# E-19_RGB_8x8_Display.net
KiCad netlist of a schematic drawn in Altium Designer
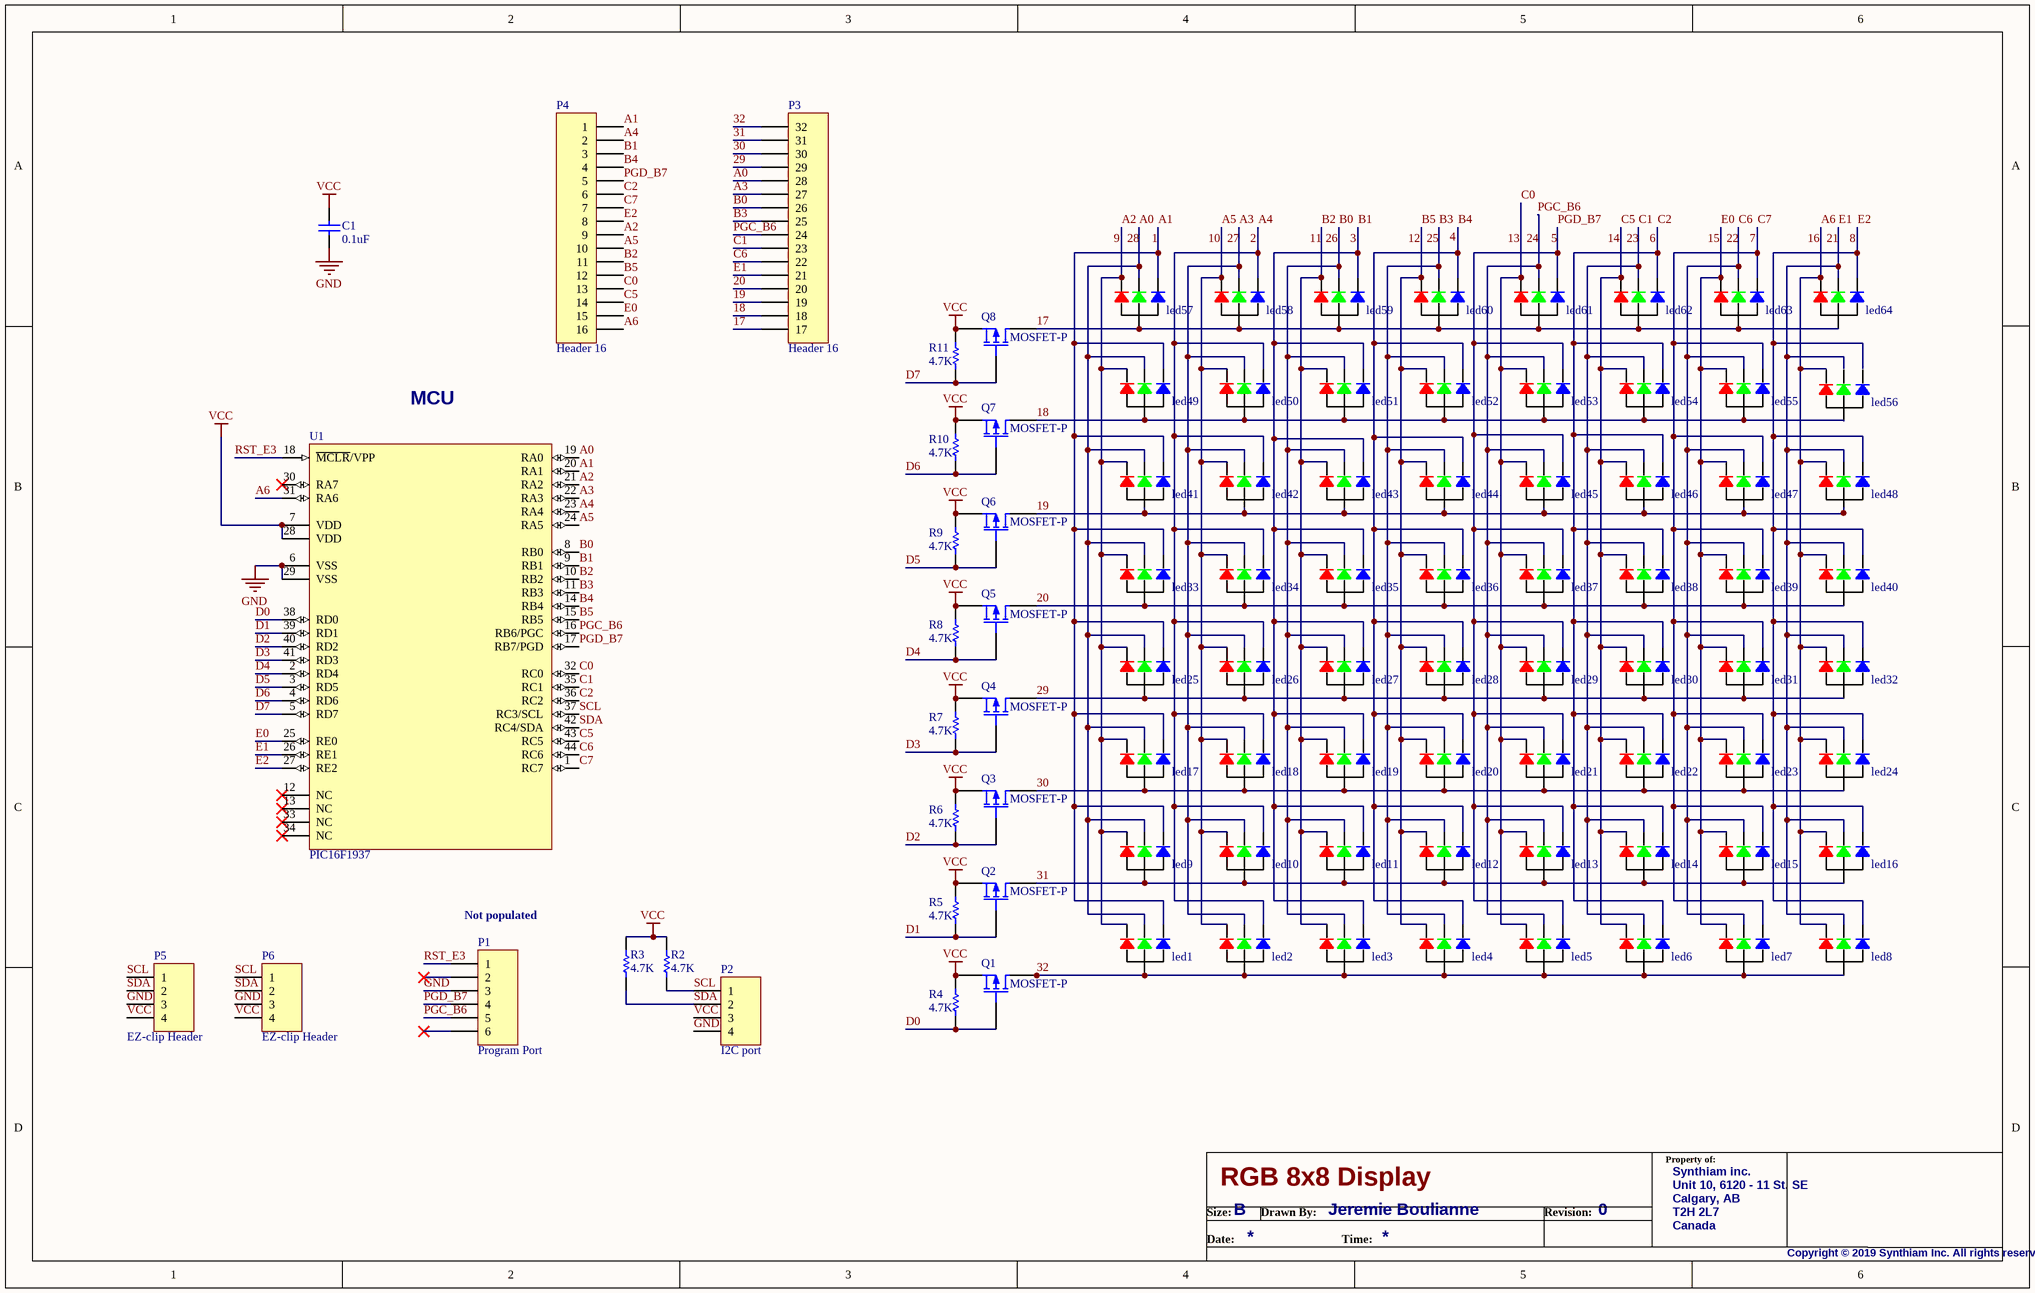
[diagram p0: E-19 RGB 8x8 Display.SchDoc]

(export (version "E")
  (design (tool "Eeschema 10.0.6"))
  (components
    (comp (ref "C1")
      (value "0.1uF")
      (footprint "0805 TIGHT")
      (description "Capacitor")
      (fields (field (name "Comment") "Cap") (field (name "PUBLISHER") "Altium Limited"))
      (libsource (lib "SB_Discrete") (part "Cap"))
    )
    (comp (ref "led1") (value "RGBLED-CA mini2") (libsource (lib "") (part "RGBLED-CA mini2_1")))
    (comp (ref "led2") (value "RGBLED-CA mini2") (libsource (lib "SB_Discrete") (part "RGBLED-CA mini2")))
    (comp (ref "led3") (value "RGBLED-CA mini2") (libsource (lib "SB_Discrete") (part "RGBLED-CA mini2")))
    (comp (ref "led4") (value "RGBLED-CA mini2") (libsource (lib "SB_Discrete") (part "RGBLED-CA mini2")))
    (comp (ref "led5") (value "RGBLED-CA mini2") (libsource (lib "SB_Discrete") (part "RGBLED-CA mini2")))
    (comp (ref "led6") (value "RGBLED-CA mini2") (libsource (lib "SB_Discrete") (part "RGBLED-CA mini2")))
    (comp (ref "led7") (value "RGBLED-CA mini2") (libsource (lib "SB_Discrete") (part "RGBLED-CA mini2")))
    (comp (ref "led8") (value "RGBLED-CA mini2") (libsource (lib "SB_Discrete") (part "RGBLED-CA mini2")))
    (comp (ref "led9") (value "RGBLED-CA mini2") (libsource (lib "SB_Discrete") (part "RGBLED-CA mini2")))
    (comp (ref "led10") (value "RGBLED-CA mini2") (libsource (lib "SB_Discrete") (part "RGBLED-CA mini2")))
    (comp (ref "led11") (value "RGBLED-CA mini2") (libsource (lib "SB_Discrete") (part "RGBLED-CA mini2")))
    (comp (ref "led12") (value "RGBLED-CA mini2") (libsource (lib "SB_Discrete") (part "RGBLED-CA mini2")))
    (comp (ref "led13") (value "RGBLED-CA mini2") (libsource (lib "SB_Discrete") (part "RGBLED-CA mini2")))
    (comp (ref "led14") (value "RGBLED-CA mini2") (libsource (lib "SB_Discrete") (part "RGBLED-CA mini2")))
    (comp (ref "led15") (value "RGBLED-CA mini2") (libsource (lib "SB_Discrete") (part "RGBLED-CA mini2")))
    (comp (ref "led16") (value "RGBLED-CA mini2") (libsource (lib "SB_Discrete") (part "RGBLED-CA mini2")))
    (comp (ref "led17") (value "RGBLED-CA mini2") (libsource (lib "SB_Discrete") (part "RGBLED-CA mini2")))
    (comp (ref "led18") (value "RGBLED-CA mini2") (libsource (lib "SB_Discrete") (part "RGBLED-CA mini2")))
    (comp (ref "led19") (value "RGBLED-CA mini2") (libsource (lib "SB_Discrete") (part "RGBLED-CA mini2")))
    (comp (ref "led20") (value "RGBLED-CA mini2") (libsource (lib "SB_Discrete") (part "RGBLED-CA mini2")))
    (comp (ref "led21") (value "RGBLED-CA mini2") (libsource (lib "SB_Discrete") (part "RGBLED-CA mini2")))
    (comp (ref "led22") (value "RGBLED-CA mini2") (libsource (lib "SB_Discrete") (part "RGBLED-CA mini2")))
    (comp (ref "led23") (value "RGBLED-CA mini2") (libsource (lib "SB_Discrete") (part "RGBLED-CA mini2")))
    (comp (ref "led24") (value "RGBLED-CA mini2") (libsource (lib "SB_Discrete") (part "RGBLED-CA mini2")))
    (comp (ref "led25") (value "RGBLED-CA mini2") (libsource (lib "SB_Discrete") (part "RGBLED-CA mini2")))
    (comp (ref "led26") (value "RGBLED-CA mini2") (libsource (lib "SB_Discrete") (part "RGBLED-CA mini2")))
    (comp (ref "led27") (value "RGBLED-CA mini2") (libsource (lib "SB_Discrete") (part "RGBLED-CA mini2")))
    (comp (ref "led28") (value "RGBLED-CA mini2") (libsource (lib "SB_Discrete") (part "RGBLED-CA mini2")))
    (comp (ref "led29") (value "RGBLED-CA mini2") (libsource (lib "SB_Discrete") (part "RGBLED-CA mini2")))
    (comp (ref "led30") (value "RGBLED-CA mini2") (libsource (lib "SB_Discrete") (part "RGBLED-CA mini2")))
    (comp (ref "led31") (value "RGBLED-CA mini2") (libsource (lib "SB_Discrete") (part "RGBLED-CA mini2")))
    (comp (ref "led32") (value "RGBLED-CA mini2") (libsource (lib "SB_Discrete") (part "RGBLED-CA mini2")))
    (comp (ref "led33") (value "RGBLED-CA mini2") (libsource (lib "SB_Discrete") (part "RGBLED-CA mini2")))
    (comp (ref "led34") (value "RGBLED-CA mini2") (libsource (lib "SB_Discrete") (part "RGBLED-CA mini2")))
    (comp (ref "led35") (value "RGBLED-CA mini2") (libsource (lib "SB_Discrete") (part "RGBLED-CA mini2")))
    (comp (ref "led36") (value "RGBLED-CA mini2") (libsource (lib "SB_Discrete") (part "RGBLED-CA mini2")))
    (comp (ref "led37") (value "RGBLED-CA mini2") (libsource (lib "SB_Discrete") (part "RGBLED-CA mini2")))
    (comp (ref "led38") (value "RGBLED-CA mini2") (libsource (lib "SB_Discrete") (part "RGBLED-CA mini2")))
    (comp (ref "led39") (value "RGBLED-CA mini2") (libsource (lib "SB_Discrete") (part "RGBLED-CA mini2")))
    (comp (ref "led40") (value "RGBLED-CA mini2") (libsource (lib "SB_Discrete") (part "RGBLED-CA mini2")))
    (comp (ref "led41") (value "RGBLED-CA mini2") (libsource (lib "SB_Discrete") (part "RGBLED-CA mini2")))
    (comp (ref "led42") (value "RGBLED-CA mini2") (libsource (lib "SB_Discrete") (part "RGBLED-CA mini2")))
    (comp (ref "led43") (value "RGBLED-CA mini2") (libsource (lib "SB_Discrete") (part "RGBLED-CA mini2")))
    (comp (ref "led44") (value "RGBLED-CA mini2") (libsource (lib "SB_Discrete") (part "RGBLED-CA mini2")))
    (comp (ref "led45") (value "RGBLED-CA mini2") (libsource (lib "SB_Discrete") (part "RGBLED-CA mini2")))
    (comp (ref "led46") (value "RGBLED-CA mini2") (libsource (lib "SB_Discrete") (part "RGBLED-CA mini2")))
    (comp (ref "led47") (value "RGBLED-CA mini2") (libsource (lib "SB_Discrete") (part "RGBLED-CA mini2")))
    (comp (ref "led48") (value "RGBLED-CA mini2") (libsource (lib "SB_Discrete") (part "RGBLED-CA mini2")))
    (comp (ref "led49") (value "RGBLED-CA mini2") (libsource (lib "SB_Discrete") (part "RGBLED-CA mini2")))
    (comp (ref "led50") (value "RGBLED-CA mini2") (libsource (lib "SB_Discrete") (part "RGBLED-CA mini2")))
    (comp (ref "led51") (value "RGBLED-CA mini2") (libsource (lib "SB_Discrete") (part "RGBLED-CA mini2")))
    (comp (ref "led52") (value "RGBLED-CA mini2") (libsource (lib "SB_Discrete") (part "RGBLED-CA mini2")))
    (comp (ref "led53") (value "RGBLED-CA mini2") (libsource (lib "SB_Discrete") (part "RGBLED-CA mini2")))
    (comp (ref "led54") (value "RGBLED-CA mini2") (libsource (lib "SB_Discrete") (part "RGBLED-CA mini2")))
    (comp (ref "led55") (value "RGBLED-CA mini2") (libsource (lib "SB_Discrete") (part "RGBLED-CA mini2")))
    (comp (ref "led56") (value "RGBLED-CA mini2") (libsource (lib "SB_Discrete") (part "RGBLED-CA mini2")))
    (comp (ref "led57") (value "RGBLED-CA mini2") (libsource (lib "SB_Discrete") (part "RGBLED-CA mini2")))
    (comp (ref "led58") (value "RGBLED-CA mini2") (libsource (lib "SB_Discrete") (part "RGBLED-CA mini2")))
    (comp (ref "led59") (value "RGBLED-CA mini2") (libsource (lib "SB_Discrete") (part "RGBLED-CA mini2")))
    (comp (ref "led60") (value "RGBLED-CA mini2") (libsource (lib "SB_Discrete") (part "RGBLED-CA mini2")))
    (comp (ref "led61") (value "RGBLED-CA mini2") (libsource (lib "SB_Discrete") (part "RGBLED-CA mini2")))
    (comp (ref "led62") (value "RGBLED-CA mini2") (libsource (lib "SB_Discrete") (part "RGBLED-CA mini2")))
    (comp (ref "led63") (value "RGBLED-CA mini2") (libsource (lib "SB_Discrete") (part "RGBLED-CA mini2")))
    (comp (ref "led64") (value "RGBLED-CA mini2") (libsource (lib "SB_Discrete") (part "RGBLED-CA mini2")))
    (comp (ref "P1")
      (value "Program Port")
      (footprint "HDR1X6")
      (description "Header, 6-Pin")
      (fields (field (name "PUBLISHER") "Altium Limited"))
      (libsource (lib "Miscellaneous Connectors") (part "Header 6"))
    )
    (comp (ref "P2")
      (value "I2C port")
      (footprint "JST-PH 4pin")
      (description "Header, 4-Pin")
      (fields (field (name "PUBLISHER") "Altium Limited"))
      (libsource (lib "Miscellaneous Connectors") (part "Header 4"))
    )
    (comp (ref "P3")
      (value "Header 16")
      (footprint "HDR1X16")
      (description "Header, 16-Pin")
      (fields (field (name "PUBLISHER") "Altium Limited"))
      (libsource (lib "Miscellaneous Connectors") (part "Header 16"))
    )
    (comp (ref "P4")
      (value "Header 16")
      (footprint "HDR1X16")
      (description "Header, 16-Pin")
      (fields (field (name "PUBLISHER") "Altium Limited"))
      (libsource (lib "") (part "Header 16_1"))
    )
    (comp (ref "P5")
      (value "EZ-clip Header")
      (footprint "HDR1X4")
      (description "Header, 4-Pin")
      (fields (field (name "PUBLISHER") "Altium Limited"))
      (libsource (lib "Miscellaneous Connectors") (part "Header 4"))
    )
    (comp (ref "P6")
      (value "EZ-clip Header")
      (footprint "HDR1X4")
      (description "Header, 4-Pin")
      (fields (field (name "PUBLISHER") "Altium Limited"))
      (libsource (lib "Miscellaneous Connectors") (part "Header 4"))
    )
    (comp (ref "Q1")
      (value "MOSFET-P")
      (footprint "SOT-23 P-FET")
      (description "P-Channel MOSFET")
      (fields (field (name "PUBLISHER") "Altium Limited"))
      (libsource (lib "Miscellaneous Devices") (part "MOSFET-P"))
    )
    (comp (ref "Q2")
      (value "MOSFET-P")
      (footprint "SOT-23 P-FET")
      (description "P-Channel MOSFET")
      (fields (field (name "PUBLISHER") "Altium Limited"))
      (libsource (lib "Miscellaneous Devices") (part "MOSFET-P"))
    )
    (comp (ref "Q3")
      (value "MOSFET-P")
      (footprint "SOT-23 P-FET")
      (description "P-Channel MOSFET")
      (fields (field (name "PUBLISHER") "Altium Limited"))
      (libsource (lib "Miscellaneous Devices") (part "MOSFET-P"))
    )
    (comp (ref "Q4")
      (value "MOSFET-P")
      (footprint "SOT-23 P-FET")
      (description "P-Channel MOSFET")
      (fields (field (name "PUBLISHER") "Altium Limited"))
      (libsource (lib "Miscellaneous Devices") (part "MOSFET-P"))
    )
    (comp (ref "Q5")
      (value "MOSFET-P")
      (footprint "SOT-23 P-FET")
      (description "P-Channel MOSFET")
      (fields (field (name "PUBLISHER") "Altium Limited"))
      (libsource (lib "Miscellaneous Devices") (part "MOSFET-P"))
    )
    (comp (ref "Q6")
      (value "MOSFET-P")
      (footprint "SOT-23 P-FET")
      (description "P-Channel MOSFET")
      (fields (field (name "PUBLISHER") "Altium Limited"))
      (libsource (lib "Miscellaneous Devices") (part "MOSFET-P"))
    )
    (comp (ref "Q7")
      (value "MOSFET-P")
      (footprint "SOT-23 P-FET")
      (description "P-Channel MOSFET")
      (fields (field (name "PUBLISHER") "Altium Limited"))
      (libsource (lib "Miscellaneous Devices") (part "MOSFET-P"))
    )
    (comp (ref "Q8")
      (value "MOSFET-P")
      (footprint "SOT-23 P-FET")
      (description "P-Channel MOSFET")
      (fields (field (name "PUBLISHER") "Altium Limited"))
      (libsource (lib "Miscellaneous Devices") (part "MOSFET-P"))
    )
    (comp (ref "R2")
      (value "4.7K")
      (footprint "0805 TIGHT")
      (description "Resistor")
      (fields (field (name "Comment") "Res1") (field (name "PUBLISHER") "Altium Limited"))
      (libsource (lib "SB_Discrete") (part "Res1"))
    )
    (comp (ref "R3")
      (value "4.7K")
      (footprint "0805 TIGHT")
      (description "Resistor")
      (fields (field (name "Comment") "Res1") (field (name "PUBLISHER") "Altium Limited"))
      (libsource (lib "SB_Discrete") (part "Res1"))
    )
    (comp (ref "R4")
      (value "4.7K")
      (footprint "0805 TIGHT")
      (description "Resistor")
      (fields (field (name "Comment") "Res1") (field (name "PUBLISHER") "Altium Limited"))
      (libsource (lib "SB_Discrete") (part "Res1"))
    )
    (comp (ref "R5")
      (value "4.7K")
      (footprint "0805 TIGHT")
      (description "Resistor")
      (fields (field (name "Comment") "Res1") (field (name "PUBLISHER") "Altium Limited"))
      (libsource (lib "SB_Discrete") (part "Res1"))
    )
    (comp (ref "R6")
      (value "4.7K")
      (footprint "0805 TIGHT")
      (description "Resistor")
      (fields (field (name "Comment") "Res1") (field (name "PUBLISHER") "Altium Limited"))
      (libsource (lib "SB_Discrete") (part "Res1"))
    )
    (comp (ref "R7")
      (value "4.7K")
      (footprint "0805 TIGHT")
      (description "Resistor")
      (fields (field (name "Comment") "Res1") (field (name "PUBLISHER") "Altium Limited"))
      (libsource (lib "SB_Discrete") (part "Res1"))
    )
    (comp (ref "R8")
      (value "4.7K")
      (footprint "0805 TIGHT")
      (description "Resistor")
      (fields (field (name "Comment") "Res1") (field (name "PUBLISHER") "Altium Limited"))
      (libsource (lib "SB_Discrete") (part "Res1"))
    )
    (comp (ref "R9")
      (value "4.7K")
      (footprint "0805 TIGHT")
      (description "Resistor")
      (fields (field (name "Comment") "Res1") (field (name "PUBLISHER") "Altium Limited"))
      (libsource (lib "SB_Discrete") (part "Res1"))
    )
    (comp (ref "R10")
      (value "4.7K")
      (footprint "0805 TIGHT")
      (description "Resistor")
      (fields (field (name "Comment") "Res1") (field (name "PUBLISHER") "Altium Limited"))
      (libsource (lib "SB_Discrete") (part "Res1"))
    )
    (comp (ref "R11")
      (value "4.7K")
      (footprint "0805 TIGHT")
      (description "Resistor")
      (fields (field (name "Comment") "Res1") (field (name "PUBLISHER") "Altium Limited"))
      (libsource (lib "SB_Discrete") (part "Res1"))
    )
    (comp (ref "U1")
      (value "PIC16F1937")
      (footprint "TQFP-PT44_M")
      (libsource (lib "SB_Engineered_Components") (part "PIC16F1937 - Matrix"))
    )
  )
  (nets
    (net (code "17") (name "/17") (class "Default")
      (node (ref "P3") (pin "16") (pinfunction "17_16") (pintype "passive"))
      (node (ref "Q8") (pin "1") (pinfunction "D_1") (pintype "passive"))
      (node (ref "led57") (pin "1") (pinfunction "1_1") (pintype "passive"))
      (node (ref "led58") (pin "1") (pinfunction "1_1") (pintype "passive"))
      (node (ref "led59") (pin "1") (pinfunction "1_1") (pintype "passive"))
      (node (ref "led60") (pin "1") (pinfunction "1_1") (pintype "passive"))
      (node (ref "led61") (pin "1") (pinfunction "1_1") (pintype "passive"))
      (node (ref "led62") (pin "1") (pinfunction "1_1") (pintype "passive"))
      (node (ref "led63") (pin "1") (pinfunction "1_1") (pintype "passive"))
      (node (ref "led64") (pin "1") (pinfunction "1_1") (pintype "passive"))
    )
    (net (code "18") (name "/18") (class "Default")
      (node (ref "P3") (pin "15") (pinfunction "18_15") (pintype "passive"))
      (node (ref "Q7") (pin "1") (pinfunction "D_1") (pintype "passive"))
      (node (ref "led49") (pin "1") (pinfunction "1_1") (pintype "passive"))
      (node (ref "led50") (pin "1") (pinfunction "1_1") (pintype "passive"))
      (node (ref "led51") (pin "1") (pinfunction "1_1") (pintype "passive"))
      (node (ref "led52") (pin "1") (pinfunction "1_1") (pintype "passive"))
      (node (ref "led53") (pin "1") (pinfunction "1_1") (pintype "passive"))
      (node (ref "led54") (pin "1") (pinfunction "1_1") (pintype "passive"))
      (node (ref "led55") (pin "1") (pinfunction "1_1") (pintype "passive"))
      (node (ref "led56") (pin "1") (pinfunction "1_1") (pintype "passive"))
    )
    (net (code "19") (name "/19") (class "Default")
      (node (ref "P3") (pin "14") (pinfunction "19_14") (pintype "passive"))
      (node (ref "Q6") (pin "1") (pinfunction "D_1") (pintype "passive"))
      (node (ref "led41") (pin "1") (pinfunction "1_1") (pintype "passive"))
      (node (ref "led42") (pin "1") (pinfunction "1_1") (pintype "passive"))
      (node (ref "led43") (pin "1") (pinfunction "1_1") (pintype "passive"))
      (node (ref "led44") (pin "1") (pinfunction "1_1") (pintype "passive"))
      (node (ref "led45") (pin "1") (pinfunction "1_1") (pintype "passive"))
      (node (ref "led46") (pin "1") (pinfunction "1_1") (pintype "passive"))
      (node (ref "led47") (pin "1") (pinfunction "1_1") (pintype "passive"))
      (node (ref "led48") (pin "1") (pinfunction "1_1") (pintype "passive"))
    )
    (net (code "20") (name "/20") (class "Default")
      (node (ref "P3") (pin "13") (pinfunction "20_13") (pintype "passive"))
      (node (ref "Q5") (pin "1") (pinfunction "D_1") (pintype "passive"))
      (node (ref "led33") (pin "1") (pinfunction "1_1") (pintype "passive"))
      (node (ref "led34") (pin "1") (pinfunction "1_1") (pintype "passive"))
      (node (ref "led35") (pin "1") (pinfunction "1_1") (pintype "passive"))
      (node (ref "led36") (pin "1") (pinfunction "1_1") (pintype "passive"))
      (node (ref "led37") (pin "1") (pinfunction "1_1") (pintype "passive"))
      (node (ref "led38") (pin "1") (pinfunction "1_1") (pintype "passive"))
      (node (ref "led39") (pin "1") (pinfunction "1_1") (pintype "passive"))
      (node (ref "led40") (pin "1") (pinfunction "1_1") (pintype "passive"))
    )
    (net (code "29") (name "/29") (class "Default")
      (node (ref "P3") (pin "4") (pinfunction "29_4") (pintype "passive"))
      (node (ref "Q4") (pin "1") (pinfunction "D_1") (pintype "passive"))
      (node (ref "led25") (pin "1") (pinfunction "1_1") (pintype "passive"))
      (node (ref "led26") (pin "1") (pinfunction "1_1") (pintype "passive"))
      (node (ref "led27") (pin "1") (pinfunction "1_1") (pintype "passive"))
      (node (ref "led28") (pin "1") (pinfunction "1_1") (pintype "passive"))
      (node (ref "led29") (pin "1") (pinfunction "1_1") (pintype "passive"))
      (node (ref "led30") (pin "1") (pinfunction "1_1") (pintype "passive"))
      (node (ref "led31") (pin "1") (pinfunction "1_1") (pintype "passive"))
      (node (ref "led32") (pin "1") (pinfunction "1_1") (pintype "passive"))
    )
    (net (code "30") (name "/30") (class "Default")
      (node (ref "P3") (pin "3") (pinfunction "30_3") (pintype "passive"))
      (node (ref "Q3") (pin "1") (pinfunction "D_1") (pintype "passive"))
      (node (ref "led17") (pin "1") (pinfunction "1_1") (pintype "passive"))
      (node (ref "led18") (pin "1") (pinfunction "1_1") (pintype "passive"))
      (node (ref "led19") (pin "1") (pinfunction "1_1") (pintype "passive"))
      (node (ref "led20") (pin "1") (pinfunction "1_1") (pintype "passive"))
      (node (ref "led21") (pin "1") (pinfunction "1_1") (pintype "passive"))
      (node (ref "led22") (pin "1") (pinfunction "1_1") (pintype "passive"))
      (node (ref "led23") (pin "1") (pinfunction "1_1") (pintype "passive"))
      (node (ref "led24") (pin "1") (pinfunction "1_1") (pintype "passive"))
    )
    (net (code "31") (name "/31") (class "Default")
      (node (ref "P3") (pin "2") (pinfunction "31_2") (pintype "passive"))
      (node (ref "Q2") (pin "1") (pinfunction "D_1") (pintype "passive"))
      (node (ref "led10") (pin "1") (pinfunction "1_1") (pintype "passive"))
      (node (ref "led11") (pin "1") (pinfunction "1_1") (pintype "passive"))
      (node (ref "led12") (pin "1") (pinfunction "1_1") (pintype "passive"))
      (node (ref "led13") (pin "1") (pinfunction "1_1") (pintype "passive"))
      (node (ref "led14") (pin "1") (pinfunction "1_1") (pintype "passive"))
      (node (ref "led15") (pin "1") (pinfunction "1_1") (pintype "passive"))
      (node (ref "led16") (pin "1") (pinfunction "1_1") (pintype "passive"))
      (node (ref "led9") (pin "1") (pinfunction "1_1") (pintype "passive"))
    )
    (net (code "32") (name "/32") (class "Default")
      (node (ref "P3") (pin "1") (pinfunction "32_1") (pintype "passive"))
      (node (ref "Q1") (pin "1") (pinfunction "D_1") (pintype "passive"))
      (node (ref "led1") (pin "1") (pinfunction "1_1") (pintype "passive"))
      (node (ref "led2") (pin "1") (pinfunction "1_1") (pintype "passive"))
      (node (ref "led3") (pin "1") (pinfunction "1_1") (pintype "passive"))
      (node (ref "led4") (pin "1") (pinfunction "1_1") (pintype "passive"))
      (node (ref "led5") (pin "1") (pinfunction "1_1") (pintype "passive"))
      (node (ref "led6") (pin "1") (pinfunction "1_1") (pintype "passive"))
      (node (ref "led7") (pin "1") (pinfunction "1_1") (pintype "passive"))
      (node (ref "led8") (pin "1") (pinfunction "1_1") (pintype "passive"))
    )
    (net (code "33") (name "/A0") (class "Default")
      (node (ref "P3") (pin "5") (pinfunction "28_5") (pintype "passive"))
      (node (ref "U1") (pin "19") (pinfunction "RA0_19") (pintype "bidirectional"))
      (node (ref "led1") (pin "4") (pinfunction "4_4") (pintype "passive"))
      (node (ref "led17") (pin "4") (pinfunction "4_4") (pintype "passive"))
      (node (ref "led25") (pin "4") (pinfunction "4_4") (pintype "passive"))
      (node (ref "led33") (pin "4") (pinfunction "4_4") (pintype "passive"))
      (node (ref "led41") (pin "4") (pinfunction "4_4") (pintype "passive"))
      (node (ref "led49") (pin "4") (pinfunction "4_4") (pintype "passive"))
      (node (ref "led57") (pin "4") (pinfunction "4_4") (pintype "passive"))
      (node (ref "led9") (pin "4") (pinfunction "4_4") (pintype "passive"))
    )
    (net (code "34") (name "/A1") (class "Default")
      (node (ref "P4") (pin "1") (pinfunction "1_1") (pintype "passive"))
      (node (ref "U1") (pin "20") (pinfunction "RA1_20") (pintype "bidirectional"))
      (node (ref "led1") (pin "2") (pinfunction "2_2") (pintype "passive"))
      (node (ref "led17") (pin "2") (pinfunction "2_2") (pintype "passive"))
      (node (ref "led25") (pin "2") (pinfunction "2_2") (pintype "passive"))
      (node (ref "led33") (pin "2") (pinfunction "2_2") (pintype "passive"))
      (node (ref "led41") (pin "2") (pinfunction "2_2") (pintype "passive"))
      (node (ref "led49") (pin "2") (pinfunction "2_2") (pintype "passive"))
      (node (ref "led57") (pin "2") (pinfunction "2_2") (pintype "passive"))
      (node (ref "led9") (pin "2") (pinfunction "2_2") (pintype "passive"))
    )
    (net (code "35") (name "/A2") (class "Default")
      (node (ref "P4") (pin "9") (pinfunction "9_9") (pintype "passive"))
      (node (ref "U1") (pin "21") (pinfunction "RA2_21") (pintype "bidirectional"))
      (node (ref "led1") (pin "3") (pinfunction "3_3") (pintype "passive"))
      (node (ref "led17") (pin "3") (pinfunction "3_3") (pintype "passive"))
      (node (ref "led25") (pin "3") (pinfunction "3_3") (pintype "passive"))
      (node (ref "led33") (pin "3") (pinfunction "3_3") (pintype "passive"))
      (node (ref "led41") (pin "3") (pinfunction "3_3") (pintype "passive"))
      (node (ref "led49") (pin "3") (pinfunction "3_3") (pintype "passive"))
      (node (ref "led57") (pin "3") (pinfunction "3_3") (pintype "passive"))
      (node (ref "led9") (pin "3") (pinfunction "3_3") (pintype "passive"))
    )
    (net (code "36") (name "/A3") (class "Default")
      (node (ref "P3") (pin "6") (pinfunction "27_6") (pintype "passive"))
      (node (ref "U1") (pin "22") (pinfunction "RA3_22") (pintype "bidirectional"))
      (node (ref "led10") (pin "4") (pinfunction "4_4") (pintype "passive"))
      (node (ref "led18") (pin "4") (pinfunction "4_4") (pintype "passive"))
      (node (ref "led2") (pin "4") (pinfunction "4_4") (pintype "passive"))
      (node (ref "led26") (pin "4") (pinfunction "4_4") (pintype "passive"))
      (node (ref "led34") (pin "4") (pinfunction "4_4") (pintype "passive"))
      (node (ref "led42") (pin "4") (pinfunction "4_4") (pintype "passive"))
      (node (ref "led50") (pin "4") (pinfunction "4_4") (pintype "passive"))
      (node (ref "led58") (pin "4") (pinfunction "4_4") (pintype "passive"))
    )
    (net (code "37") (name "/A4") (class "Default")
      (node (ref "P4") (pin "2") (pinfunction "2_2") (pintype "passive"))
      (node (ref "U1") (pin "23") (pinfunction "RA4_23") (pintype "bidirectional"))
      (node (ref "led10") (pin "2") (pinfunction "2_2") (pintype "passive"))
      (node (ref "led18") (pin "2") (pinfunction "2_2") (pintype "passive"))
      (node (ref "led2") (pin "2") (pinfunction "2_2") (pintype "passive"))
      (node (ref "led26") (pin "2") (pinfunction "2_2") (pintype "passive"))
      (node (ref "led34") (pin "2") (pinfunction "2_2") (pintype "passive"))
      (node (ref "led42") (pin "2") (pinfunction "2_2") (pintype "passive"))
      (node (ref "led50") (pin "2") (pinfunction "2_2") (pintype "passive"))
      (node (ref "led58") (pin "2") (pinfunction "2_2") (pintype "passive"))
    )
    (net (code "38") (name "/A5") (class "Default")
      (node (ref "P4") (pin "10") (pinfunction "10_10") (pintype "passive"))
      (node (ref "U1") (pin "24") (pinfunction "RA5_24") (pintype "bidirectional"))
      (node (ref "led10") (pin "3") (pinfunction "3_3") (pintype "passive"))
      (node (ref "led18") (pin "3") (pinfunction "3_3") (pintype "passive"))
      (node (ref "led2") (pin "3") (pinfunction "3_3") (pintype "passive"))
      (node (ref "led26") (pin "3") (pinfunction "3_3") (pintype "passive"))
      (node (ref "led34") (pin "3") (pinfunction "3_3") (pintype "passive"))
      (node (ref "led42") (pin "3") (pinfunction "3_3") (pintype "passive"))
      (node (ref "led50") (pin "3") (pinfunction "3_3") (pintype "passive"))
      (node (ref "led58") (pin "3") (pinfunction "3_3") (pintype "passive"))
    )
    (net (code "39") (name "/A6") (class "Default")
      (node (ref "P4") (pin "16") (pinfunction "16_16") (pintype "passive"))
      (node (ref "U1") (pin "31") (pinfunction "RA6_31") (pintype "bidirectional"))
      (node (ref "led16") (pin "3") (pinfunction "3_3") (pintype "passive"))
      (node (ref "led24") (pin "3") (pinfunction "3_3") (pintype "passive"))
      (node (ref "led32") (pin "3") (pinfunction "3_3") (pintype "passive"))
      (node (ref "led40") (pin "3") (pinfunction "3_3") (pintype "passive"))
      (node (ref "led48") (pin "3") (pinfunction "3_3") (pintype "passive"))
      (node (ref "led64") (pin "3") (pinfunction "3_3") (pintype "passive"))
      (node (ref "led8") (pin "3") (pinfunction "3_3") (pintype "passive"))
    )
    (net (code "40") (name "/B0") (class "Default")
      (node (ref "P3") (pin "7") (pinfunction "26_7") (pintype "passive"))
      (node (ref "U1") (pin "8") (pinfunction "RB0_8") (pintype "bidirectional"))
      (node (ref "led11") (pin "4") (pinfunction "4_4") (pintype "passive"))
      (node (ref "led19") (pin "4") (pinfunction "4_4") (pintype "passive"))
      (node (ref "led27") (pin "4") (pinfunction "4_4") (pintype "passive"))
      (node (ref "led3") (pin "4") (pinfunction "4_4") (pintype "passive"))
      (node (ref "led35") (pin "4") (pinfunction "4_4") (pintype "passive"))
      (node (ref "led43") (pin "4") (pinfunction "4_4") (pintype "passive"))
      (node (ref "led51") (pin "4") (pinfunction "4_4") (pintype "passive"))
      (node (ref "led59") (pin "4") (pinfunction "4_4") (pintype "passive"))
    )
    (net (code "41") (name "/B1") (class "Default")
      (node (ref "P4") (pin "3") (pinfunction "3_3") (pintype "passive"))
      (node (ref "U1") (pin "9") (pinfunction "RB1_9") (pintype "bidirectional"))
      (node (ref "led11") (pin "2") (pinfunction "2_2") (pintype "passive"))
      (node (ref "led19") (pin "2") (pinfunction "2_2") (pintype "passive"))
      (node (ref "led27") (pin "2") (pinfunction "2_2") (pintype "passive"))
      (node (ref "led3") (pin "2") (pinfunction "2_2") (pintype "passive"))
      (node (ref "led35") (pin "2") (pinfunction "2_2") (pintype "passive"))
      (node (ref "led43") (pin "2") (pinfunction "2_2") (pintype "passive"))
      (node (ref "led51") (pin "2") (pinfunction "2_2") (pintype "passive"))
      (node (ref "led59") (pin "2") (pinfunction "2_2") (pintype "passive"))
    )
    (net (code "42") (name "/B2") (class "Default")
      (node (ref "P4") (pin "11") (pinfunction "11_11") (pintype "passive"))
      (node (ref "U1") (pin "10") (pinfunction "RB2_10") (pintype "bidirectional"))
      (node (ref "led11") (pin "3") (pinfunction "3_3") (pintype "passive"))
      (node (ref "led19") (pin "3") (pinfunction "3_3") (pintype "passive"))
      (node (ref "led27") (pin "3") (pinfunction "3_3") (pintype "passive"))
      (node (ref "led3") (pin "3") (pinfunction "3_3") (pintype "passive"))
      (node (ref "led35") (pin "3") (pinfunction "3_3") (pintype "passive"))
      (node (ref "led43") (pin "3") (pinfunction "3_3") (pintype "passive"))
      (node (ref "led51") (pin "3") (pinfunction "3_3") (pintype "passive"))
      (node (ref "led59") (pin "3") (pinfunction "3_3") (pintype "passive"))
    )
    (net (code "43") (name "/B3") (class "Default")
      (node (ref "P3") (pin "8") (pinfunction "25_8") (pintype "passive"))
      (node (ref "U1") (pin "11") (pinfunction "RB3_11") (pintype "bidirectional"))
      (node (ref "led12") (pin "4") (pinfunction "4_4") (pintype "passive"))
      (node (ref "led20") (pin "4") (pinfunction "4_4") (pintype "passive"))
      (node (ref "led28") (pin "4") (pinfunction "4_4") (pintype "passive"))
      (node (ref "led36") (pin "4") (pinfunction "4_4") (pintype "passive"))
      (node (ref "led4") (pin "4") (pinfunction "4_4") (pintype "passive"))
      (node (ref "led44") (pin "4") (pinfunction "4_4") (pintype "passive"))
      (node (ref "led52") (pin "4") (pinfunction "4_4") (pintype "passive"))
      (node (ref "led60") (pin "4") (pinfunction "4_4") (pintype "passive"))
    )
    (net (code "44") (name "/B4") (class "Default")
      (node (ref "P4") (pin "4") (pinfunction "4_4") (pintype "passive"))
      (node (ref "U1") (pin "14") (pinfunction "RB4_14") (pintype "bidirectional"))
      (node (ref "led12") (pin "2") (pinfunction "2_2") (pintype "passive"))
      (node (ref "led20") (pin "2") (pinfunction "2_2") (pintype "passive"))
      (node (ref "led28") (pin "2") (pinfunction "2_2") (pintype "passive"))
      (node (ref "led36") (pin "2") (pinfunction "2_2") (pintype "passive"))
      (node (ref "led4") (pin "2") (pinfunction "2_2") (pintype "passive"))
      (node (ref "led44") (pin "2") (pinfunction "2_2") (pintype "passive"))
      (node (ref "led52") (pin "2") (pinfunction "2_2") (pintype "passive"))
      (node (ref "led60") (pin "2") (pinfunction "2_2") (pintype "passive"))
    )
    (net (code "45") (name "/B5") (class "Default")
      (node (ref "P4") (pin "12") (pinfunction "12_12") (pintype "passive"))
      (node (ref "U1") (pin "15") (pinfunction "RB5_15") (pintype "bidirectional"))
      (node (ref "led12") (pin "3") (pinfunction "3_3") (pintype "passive"))
      (node (ref "led20") (pin "3") (pinfunction "3_3") (pintype "passive"))
      (node (ref "led28") (pin "3") (pinfunction "3_3") (pintype "passive"))
      (node (ref "led36") (pin "3") (pinfunction "3_3") (pintype "passive"))
      (node (ref "led4") (pin "3") (pinfunction "3_3") (pintype "passive"))
      (node (ref "led44") (pin "3") (pinfunction "3_3") (pintype "passive"))
      (node (ref "led52") (pin "3") (pinfunction "3_3") (pintype "passive"))
      (node (ref "led60") (pin "3") (pinfunction "3_3") (pintype "passive"))
    )
    (net (code "46") (name "/C0") (class "Default")
      (node (ref "P4") (pin "13") (pinfunction "13_13") (pintype "passive"))
      (node (ref "U1") (pin "32") (pinfunction "RC0_32") (pintype "bidirectional"))
      (node (ref "led13") (pin "3") (pinfunction "3_3") (pintype "passive"))
      (node (ref "led21") (pin "3") (pinfunction "3_3") (pintype "passive"))
      (node (ref "led29") (pin "3") (pinfunction "3_3") (pintype "passive"))
      (node (ref "led37") (pin "3") (pinfunction "3_3") (pintype "passive"))
      (node (ref "led45") (pin "3") (pinfunction "3_3") (pintype "passive"))
      (node (ref "led5") (pin "3") (pinfunction "3_3") (pintype "passive"))
      (node (ref "led53") (pin "3") (pinfunction "3_3") (pintype "passive"))
      (node (ref "led61") (pin "3") (pinfunction "3_3") (pintype "passive"))
    )
    (net (code "47") (name "/C1") (class "Default")
      (node (ref "P3") (pin "10") (pinfunction "23_10") (pintype "passive"))
      (node (ref "U1") (pin "35") (pinfunction "RC1_35") (pintype "bidirectional"))
      (node (ref "led14") (pin "4") (pinfunction "4_4") (pintype "passive"))
      (node (ref "led22") (pin "4") (pinfunction "4_4") (pintype "passive"))
      (node (ref "led30") (pin "4") (pinfunction "4_4") (pintype "passive"))
      (node (ref "led38") (pin "4") (pinfunction "4_4") (pintype "passive"))
      (node (ref "led46") (pin "4") (pinfunction "4_4") (pintype "passive"))
      (node (ref "led54") (pin "4") (pinfunction "4_4") (pintype "passive"))
      (node (ref "led6") (pin "4") (pinfunction "4_4") (pintype "passive"))
      (node (ref "led62") (pin "4") (pinfunction "4_4") (pintype "passive"))
    )
    (net (code "48") (name "/C2") (class "Default")
      (node (ref "P4") (pin "6") (pinfunction "6_6") (pintype "passive"))
      (node (ref "U1") (pin "36") (pinfunction "RC2_36") (pintype "bidirectional"))
      (node (ref "led14") (pin "2") (pinfunction "2_2") (pintype "passive"))
      (node (ref "led22") (pin "2") (pinfunction "2_2") (pintype "passive"))
      (node (ref "led30") (pin "2") (pinfunction "2_2") (pintype "passive"))
      (node (ref "led38") (pin "2") (pinfunction "2_2") (pintype "passive"))
      (node (ref "led46") (pin "2") (pinfunction "2_2") (pintype "passive"))
      (node (ref "led54") (pin "2") (pinfunction "2_2") (pintype "passive"))
      (node (ref "led6") (pin "2") (pinfunction "2_2") (pintype "passive"))
      (node (ref "led62") (pin "2") (pinfunction "2_2") (pintype "passive"))
    )
    (net (code "49") (name "/C5") (class "Default")
      (node (ref "P4") (pin "14") (pinfunction "14_14") (pintype "passive"))
      (node (ref "U1") (pin "43") (pinfunction "RC5_43") (pintype "bidirectional"))
      (node (ref "led14") (pin "3") (pinfunction "3_3") (pintype "passive"))
      (node (ref "led22") (pin "3") (pinfunction "3_3") (pintype "passive"))
      (node (ref "led30") (pin "3") (pinfunction "3_3") (pintype "passive"))
      (node (ref "led38") (pin "3") (pinfunction "3_3") (pintype "passive"))
      (node (ref "led46") (pin "3") (pinfunction "3_3") (pintype "passive"))
      (node (ref "led54") (pin "3") (pinfunction "3_3") (pintype "passive"))
      (node (ref "led6") (pin "3") (pinfunction "3_3") (pintype "passive"))
      (node (ref "led62") (pin "3") (pinfunction "3_3") (pintype "passive"))
    )
    (net (code "50") (name "/C6") (class "Default")
      (node (ref "P3") (pin "11") (pinfunction "22_11") (pintype "passive"))
      (node (ref "U1") (pin "44") (pinfunction "RC6_44") (pintype "bidirectional"))
      (node (ref "led15") (pin "4") (pinfunction "4_4") (pintype "passive"))
      (node (ref "led23") (pin "4") (pinfunction "4_4") (pintype "passive"))
      (node (ref "led31") (pin "4") (pinfunction "4_4") (pintype "passive"))
      (node (ref "led39") (pin "4") (pinfunction "4_4") (pintype "passive"))
      (node (ref "led47") (pin "4") (pinfunction "4_4") (pintype "passive"))
      (node (ref "led55") (pin "4") (pinfunction "4_4") (pintype "passive"))
      (node (ref "led63") (pin "4") (pinfunction "4_4") (pintype "passive"))
      (node (ref "led7") (pin "4") (pinfunction "4_4") (pintype "passive"))
    )
    (net (code "51") (name "/C7") (class "Default")
      (node (ref "P4") (pin "7") (pinfunction "7_7") (pintype "passive"))
      (node (ref "U1") (pin "1") (pinfunction "RC7_1") (pintype "bidirectional"))
      (node (ref "led15") (pin "2") (pinfunction "2_2") (pintype "passive"))
      (node (ref "led23") (pin "2") (pinfunction "2_2") (pintype "passive"))
      (node (ref "led31") (pin "2") (pinfunction "2_2") (pintype "passive"))
      (node (ref "led39") (pin "2") (pinfunction "2_2") (pintype "passive"))
      (node (ref "led47") (pin "2") (pinfunction "2_2") (pintype "passive"))
      (node (ref "led55") (pin "2") (pinfunction "2_2") (pintype "passive"))
      (node (ref "led63") (pin "2") (pinfunction "2_2") (pintype "passive"))
      (node (ref "led7") (pin "2") (pinfunction "2_2") (pintype "passive"))
    )
    (net (code "52") (name "/D0") (class "Default")
      (node (ref "Q1") (pin "2") (pinfunction "G_2") (pintype "passive"))
      (node (ref "R4") (pin "1") (pinfunction "1_1") (pintype "passive"))
      (node (ref "U1") (pin "38") (pinfunction "RD0_38") (pintype "bidirectional"))
    )
    (net (code "53") (name "/D1") (class "Default")
      (node (ref "Q2") (pin "2") (pinfunction "G_2") (pintype "passive"))
      (node (ref "R5") (pin "1") (pinfunction "1_1") (pintype "passive"))
      (node (ref "U1") (pin "39") (pinfunction "RD1_39") (pintype "bidirectional"))
    )
    (net (code "54") (name "/D2") (class "Default")
      (node (ref "Q3") (pin "2") (pinfunction "G_2") (pintype "passive"))
      (node (ref "R6") (pin "1") (pinfunction "1_1") (pintype "passive"))
      (node (ref "U1") (pin "40") (pinfunction "RD2_40") (pintype "bidirectional"))
    )
    (net (code "55") (name "/D3") (class "Default")
      (node (ref "Q4") (pin "2") (pinfunction "G_2") (pintype "passive"))
      (node (ref "R7") (pin "1") (pinfunction "1_1") (pintype "passive"))
      (node (ref "U1") (pin "41") (pinfunction "RD3_41") (pintype "bidirectional"))
    )
    (net (code "56") (name "/D4") (class "Default")
      (node (ref "Q5") (pin "2") (pinfunction "G_2") (pintype "passive"))
      (node (ref "R8") (pin "1") (pinfunction "1_1") (pintype "passive"))
      (node (ref "U1") (pin "2") (pinfunction "RD4_2") (pintype "bidirectional"))
    )
    (net (code "57") (name "/D5") (class "Default")
      (node (ref "Q6") (pin "2") (pinfunction "G_2") (pintype "passive"))
      (node (ref "R9") (pin "1") (pinfunction "1_1") (pintype "passive"))
      (node (ref "U1") (pin "3") (pinfunction "RD5_3") (pintype "bidirectional"))
    )
    (net (code "58") (name "/D6") (class "Default")
      (node (ref "Q7") (pin "2") (pinfunction "G_2") (pintype "passive"))
      (node (ref "R10") (pin "1") (pinfunction "1_1") (pintype "passive"))
      (node (ref "U1") (pin "4") (pinfunction "RD6_4") (pintype "bidirectional"))
    )
    (net (code "59") (name "/D7") (class "Default")
      (node (ref "Q8") (pin "2") (pinfunction "G_2") (pintype "passive"))
      (node (ref "R11") (pin "1") (pinfunction "1_1") (pintype "passive"))
      (node (ref "U1") (pin "5") (pinfunction "RD7_5") (pintype "bidirectional"))
    )
    (net (code "60") (name "/E0") (class "Default")
      (node (ref "P4") (pin "15") (pinfunction "15_15") (pintype "passive"))
      (node (ref "U1") (pin "25") (pinfunction "RE0_25") (pintype "bidirectional"))
      (node (ref "led15") (pin "3") (pinfunction "3_3") (pintype "passive"))
      (node (ref "led23") (pin "3") (pinfunction "3_3") (pintype "passive"))
      (node (ref "led31") (pin "3") (pinfunction "3_3") (pintype "passive"))
      (node (ref "led39") (pin "3") (pinfunction "3_3") (pintype "passive"))
      (node (ref "led47") (pin "3") (pinfunction "3_3") (pintype "passive"))
      (node (ref "led55") (pin "3") (pinfunction "3_3") (pintype "passive"))
      (node (ref "led63") (pin "3") (pinfunction "3_3") (pintype "passive"))
      (node (ref "led7") (pin "3") (pinfunction "3_3") (pintype "passive"))
    )
    (net (code "61") (name "/E1") (class "Default")
      (node (ref "P3") (pin "12") (pinfunction "21_12") (pintype "passive"))
      (node (ref "U1") (pin "26") (pinfunction "RE1_26") (pintype "bidirectional"))
      (node (ref "led16") (pin "4") (pinfunction "4_4") (pintype "passive"))
      (node (ref "led24") (pin "4") (pinfunction "4_4") (pintype "passive"))
      (node (ref "led32") (pin "4") (pinfunction "4_4") (pintype "passive"))
      (node (ref "led40") (pin "4") (pinfunction "4_4") (pintype "passive"))
      (node (ref "led48") (pin "4") (pinfunction "4_4") (pintype "passive"))
      (node (ref "led64") (pin "4") (pinfunction "4_4") (pintype "passive"))
      (node (ref "led8") (pin "4") (pinfunction "4_4") (pintype "passive"))
    )
    (net (code "62") (name "/E2") (class "Default")
      (node (ref "P4") (pin "8") (pinfunction "8_8") (pintype "passive"))
      (node (ref "U1") (pin "27") (pinfunction "RE2_27") (pintype "bidirectional"))
      (node (ref "led16") (pin "2") (pinfunction "2_2") (pintype "passive"))
      (node (ref "led24") (pin "2") (pinfunction "2_2") (pintype "passive"))
      (node (ref "led32") (pin "2") (pinfunction "2_2") (pintype "passive"))
      (node (ref "led40") (pin "2") (pinfunction "2_2") (pintype "passive"))
      (node (ref "led48") (pin "2") (pinfunction "2_2") (pintype "passive"))
      (node (ref "led64") (pin "2") (pinfunction "2_2") (pintype "passive"))
      (node (ref "led8") (pin "2") (pinfunction "2_2") (pintype "passive"))
    )
    (net (code "63") (name "/PGC_B6") (class "Default")
      (node (ref "P1") (pin "5") (pinfunction "5_5") (pintype "passive"))
      (node (ref "P3") (pin "9") (pinfunction "24_9") (pintype "passive"))
      (node (ref "U1") (pin "16") (pinfunction "RB6/PGC_16") (pintype "bidirectional"))
      (node (ref "led13") (pin "4") (pinfunction "4_4") (pintype "passive"))
      (node (ref "led21") (pin "4") (pinfunction "4_4") (pintype "passive"))
      (node (ref "led29") (pin "4") (pinfunction "4_4") (pintype "passive"))
      (node (ref "led37") (pin "4") (pinfunction "4_4") (pintype "passive"))
      (node (ref "led45") (pin "4") (pinfunction "4_4") (pintype "passive"))
      (node (ref "led5") (pin "4") (pinfunction "4_4") (pintype "passive"))
      (node (ref "led53") (pin "4") (pinfunction "4_4") (pintype "passive"))
      (node (ref "led61") (pin "4") (pinfunction "4_4") (pintype "passive"))
    )
    (net (code "64") (name "/PGD_B7") (class "Default")
      (node (ref "P1") (pin "4") (pinfunction "4_4") (pintype "passive"))
      (node (ref "P4") (pin "5") (pinfunction "5_5") (pintype "passive"))
      (node (ref "U1") (pin "17") (pinfunction "RB7/PGD_17") (pintype "bidirectional"))
      (node (ref "led13") (pin "2") (pinfunction "2_2") (pintype "passive"))
      (node (ref "led21") (pin "2") (pinfunction "2_2") (pintype "passive"))
      (node (ref "led29") (pin "2") (pinfunction "2_2") (pintype "passive"))
      (node (ref "led37") (pin "2") (pinfunction "2_2") (pintype "passive"))
      (node (ref "led45") (pin "2") (pinfunction "2_2") (pintype "passive"))
      (node (ref "led5") (pin "2") (pinfunction "2_2") (pintype "passive"))
      (node (ref "led53") (pin "2") (pinfunction "2_2") (pintype "passive"))
      (node (ref "led61") (pin "2") (pinfunction "2_2") (pintype "passive"))
    )
    (net (code "65") (name "/RST_E3") (class "Default")
      (node (ref "P1") (pin "1") (pinfunction "1_1") (pintype "passive"))
      (node (ref "U1") (pin "18") (pinfunction "~{MCLR}/VPP_18") (pintype "input"))
    )
    (net (code "66") (name "/SCL") (class "Default")
      (node (ref "P2") (pin "1") (pinfunction "1_1") (pintype "passive"))
      (node (ref "P5") (pin "1") (pinfunction "1_1") (pintype "passive"))
      (node (ref "P6") (pin "1") (pinfunction "1_1") (pintype "passive"))
      (node (ref "R2") (pin "1") (pinfunction "1_1") (pintype "passive"))
      (node (ref "U1") (pin "37") (pinfunction "RC3/SCL_37") (pintype "bidirectional"))
    )
    (net (code "67") (name "/SDA") (class "Default")
      (node (ref "P2") (pin "2") (pinfunction "2_2") (pintype "passive"))
      (node (ref "P5") (pin "2") (pinfunction "2_2") (pintype "passive"))
      (node (ref "P6") (pin "2") (pinfunction "2_2") (pintype "passive"))
      (node (ref "R3") (pin "1") (pinfunction "1_1") (pintype "passive"))
      (node (ref "U1") (pin "42") (pinfunction "RC4/SDA_42") (pintype "bidirectional"))
    )
    (net (code "68") (name "GND") (class "Default")
      (node (ref "C1") (pin "2") (pinfunction "2_2") (pintype "passive"))
      (node (ref "P1") (pin "3") (pinfunction "3_3") (pintype "passive"))
      (node (ref "P2") (pin "4") (pinfunction "4_4") (pintype "passive"))
      (node (ref "P5") (pin "3") (pinfunction "3_3") (pintype "passive"))
      (node (ref "P6") (pin "3") (pinfunction "3_3") (pintype "passive"))
      (node (ref "U1") (pin "29") (pinfunction "VSS_29") (pintype "power_in"))
      (node (ref "U1") (pin "6") (pinfunction "VSS_6") (pintype "power_in"))
    )
    (net (code "69") (name "VCC") (class "Default")
      (node (ref "C1") (pin "1") (pinfunction "1_1") (pintype "passive"))
      (node (ref "P2") (pin "3") (pinfunction "3_3") (pintype "passive"))
      (node (ref "P5") (pin "4") (pinfunction "4_4") (pintype "passive"))
      (node (ref "P6") (pin "4") (pinfunction "4_4") (pintype "passive"))
      (node (ref "Q1") (pin "3") (pinfunction "S_3") (pintype "passive"))
      (node (ref "Q2") (pin "3") (pinfunction "S_3") (pintype "passive"))
      (node (ref "Q3") (pin "3") (pinfunction "S_3") (pintype "passive"))
      (node (ref "Q4") (pin "3") (pinfunction "S_3") (pintype "passive"))
      (node (ref "Q5") (pin "3") (pinfunction "S_3") (pintype "passive"))
      (node (ref "Q6") (pin "3") (pinfunction "S_3") (pintype "passive"))
      (node (ref "Q7") (pin "3") (pinfunction "S_3") (pintype "passive"))
      (node (ref "Q8") (pin "3") (pinfunction "S_3") (pintype "passive"))
      (node (ref "R10") (pin "2") (pinfunction "2_2") (pintype "passive"))
      (node (ref "R11") (pin "2") (pinfunction "2_2") (pintype "passive"))
      (node (ref "R2") (pin "2") (pinfunction "2_2") (pintype "passive"))
      (node (ref "R3") (pin "2") (pinfunction "2_2") (pintype "passive"))
      (node (ref "R4") (pin "2") (pinfunction "2_2") (pintype "passive"))
      (node (ref "R5") (pin "2") (pinfunction "2_2") (pintype "passive"))
      (node (ref "R6") (pin "2") (pinfunction "2_2") (pintype "passive"))
      (node (ref "R7") (pin "2") (pinfunction "2_2") (pintype "passive"))
      (node (ref "R8") (pin "2") (pinfunction "2_2") (pintype "passive"))
      (node (ref "R9") (pin "2") (pinfunction "2_2") (pintype "passive"))
      (node (ref "U1") (pin "28") (pinfunction "VDD_28") (pintype "power_in"))
      (node (ref "U1") (pin "7") (pinfunction "VDD_7") (pintype "power_in"))
    )
    (net (code "70") (name "unconnected-(P1-Pad2)") (class "Default")
      (node (ref "P1") (pin "2") (pinfunction "2_2") (pintype "passive+no_connect"))
    )
    (net (code "71") (name "unconnected-(P1-Pad6)") (class "Default")
      (node (ref "P1") (pin "6") (pinfunction "6_6") (pintype "passive+no_connect"))
    )
    (net (code "72") (name "unconnected-(U1-NC-Pad12)") (class "Default")
      (node (ref "U1") (pin "12") (pinfunction "NC_12") (pintype "passive+no_connect"))
    )
    (net (code "73") (name "unconnected-(U1-NC-Pad13)") (class "Default")
      (node (ref "U1") (pin "13") (pinfunction "NC_13") (pintype "passive+no_connect"))
    )
    (net (code "74") (name "unconnected-(U1-NC-Pad33)") (class "Default")
      (node (ref "U1") (pin "33") (pinfunction "NC_33") (pintype "passive+no_connect"))
    )
    (net (code "75") (name "unconnected-(U1-NC-Pad34)") (class "Default")
      (node (ref "U1") (pin "34") (pinfunction "NC_34") (pintype "passive+no_connect"))
    )
    (net (code "76") (name "unconnected-(U1-RA7-Pad30)") (class "Default")
      (node (ref "U1") (pin "30") (pinfunction "RA7_30") (pintype "bidirectional+no_connect"))
    )
    (net (code "77") (name "unconnected-(led56-Pad2)") (class "Default")
      (node (ref "led56") (pin "2") (pinfunction "2_2") (pintype "passive"))
    )
    (net (code "78") (name "unconnected-(led56-Pad3)") (class "Default")
      (node (ref "led56") (pin "3") (pinfunction "3_3") (pintype "passive"))
    )
    (net (code "79") (name "unconnected-(led56-Pad4)") (class "Default")
      (node (ref "led56") (pin "4") (pinfunction "4_4") (pintype "passive"))
    )
  )
)
